# Programmer_HCS.net
KiCad netlist of a schematic drawn in EAGLE
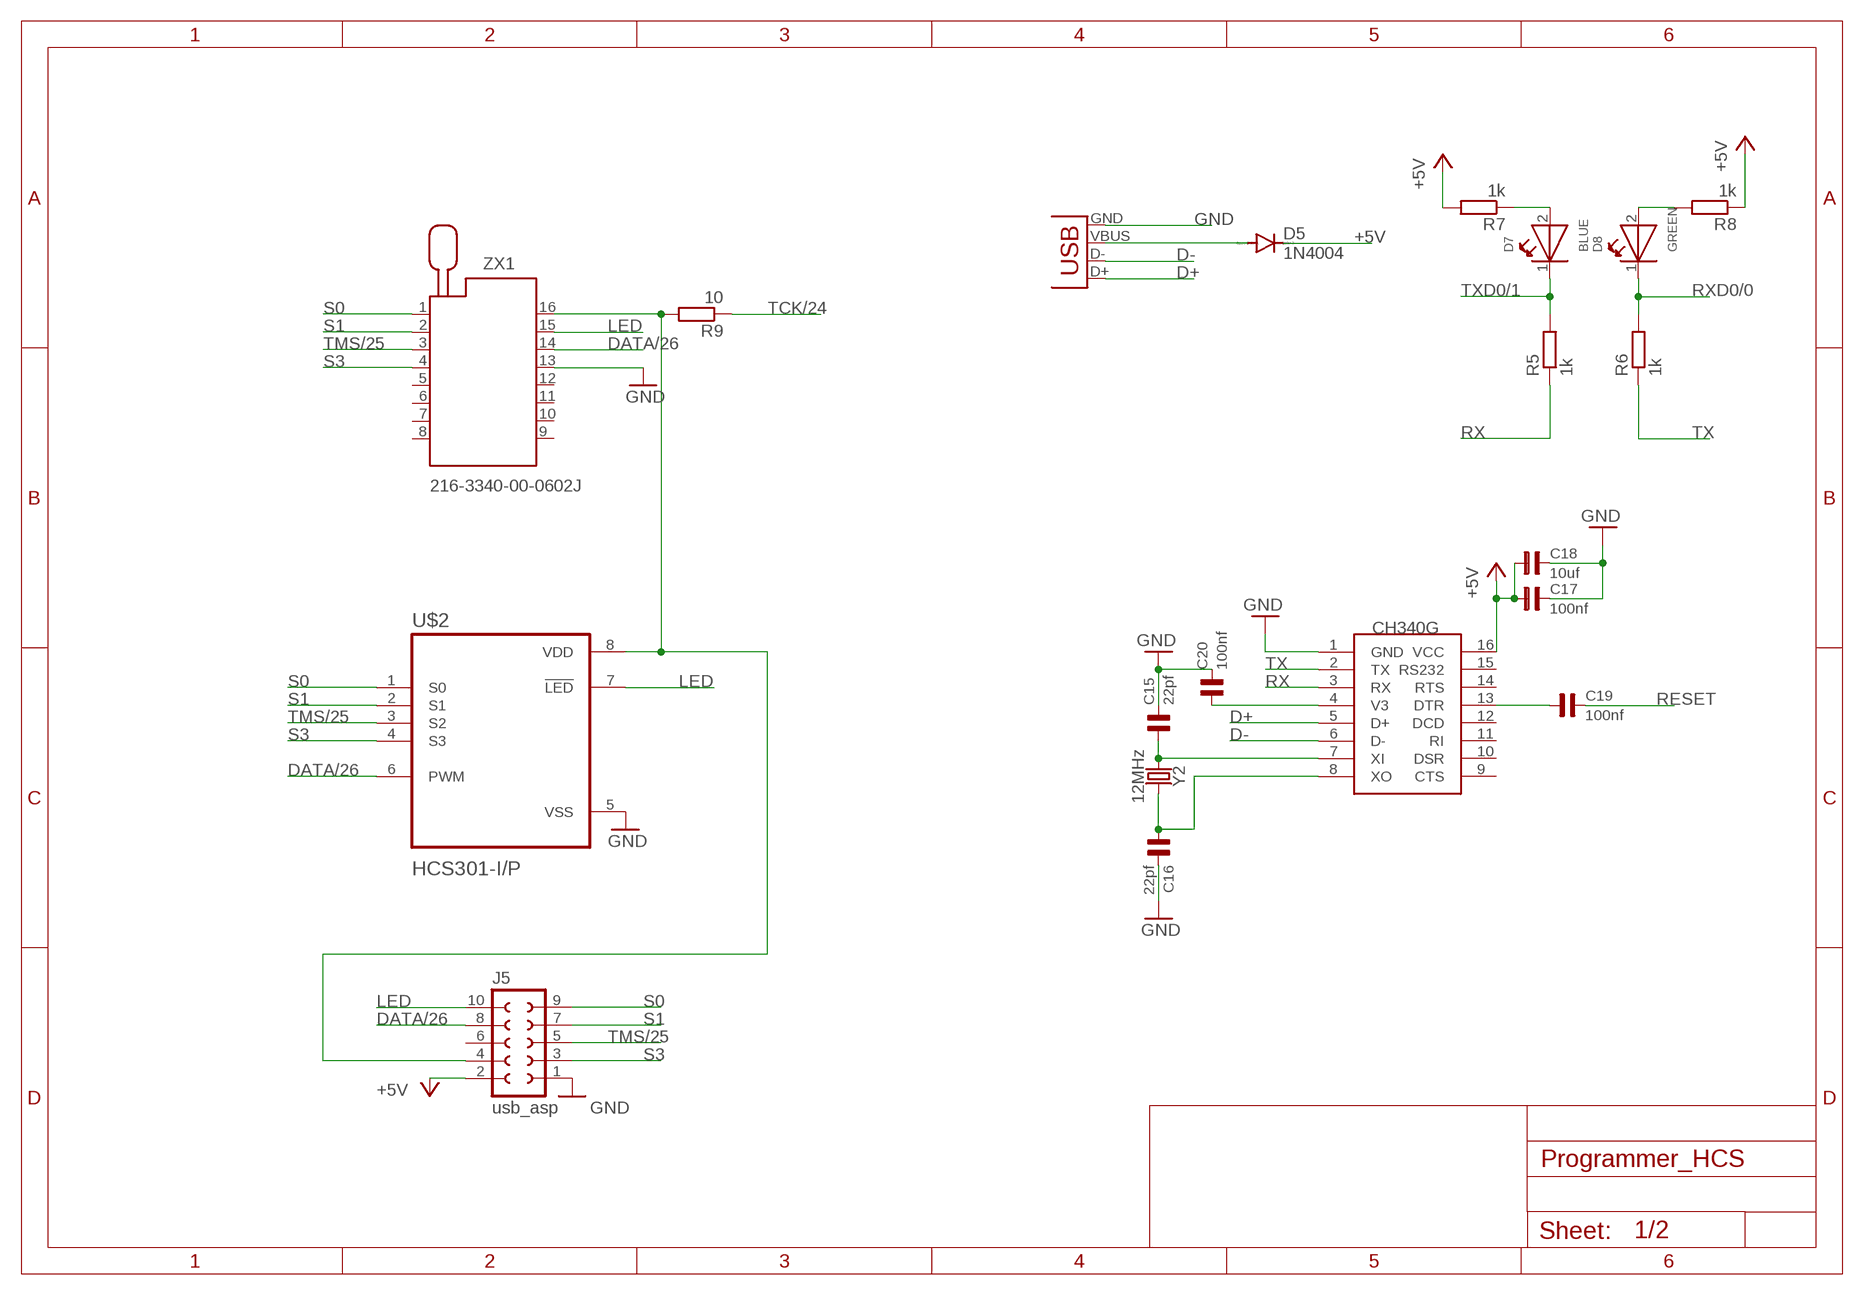
[diagram p0: schematic, sheet 1]
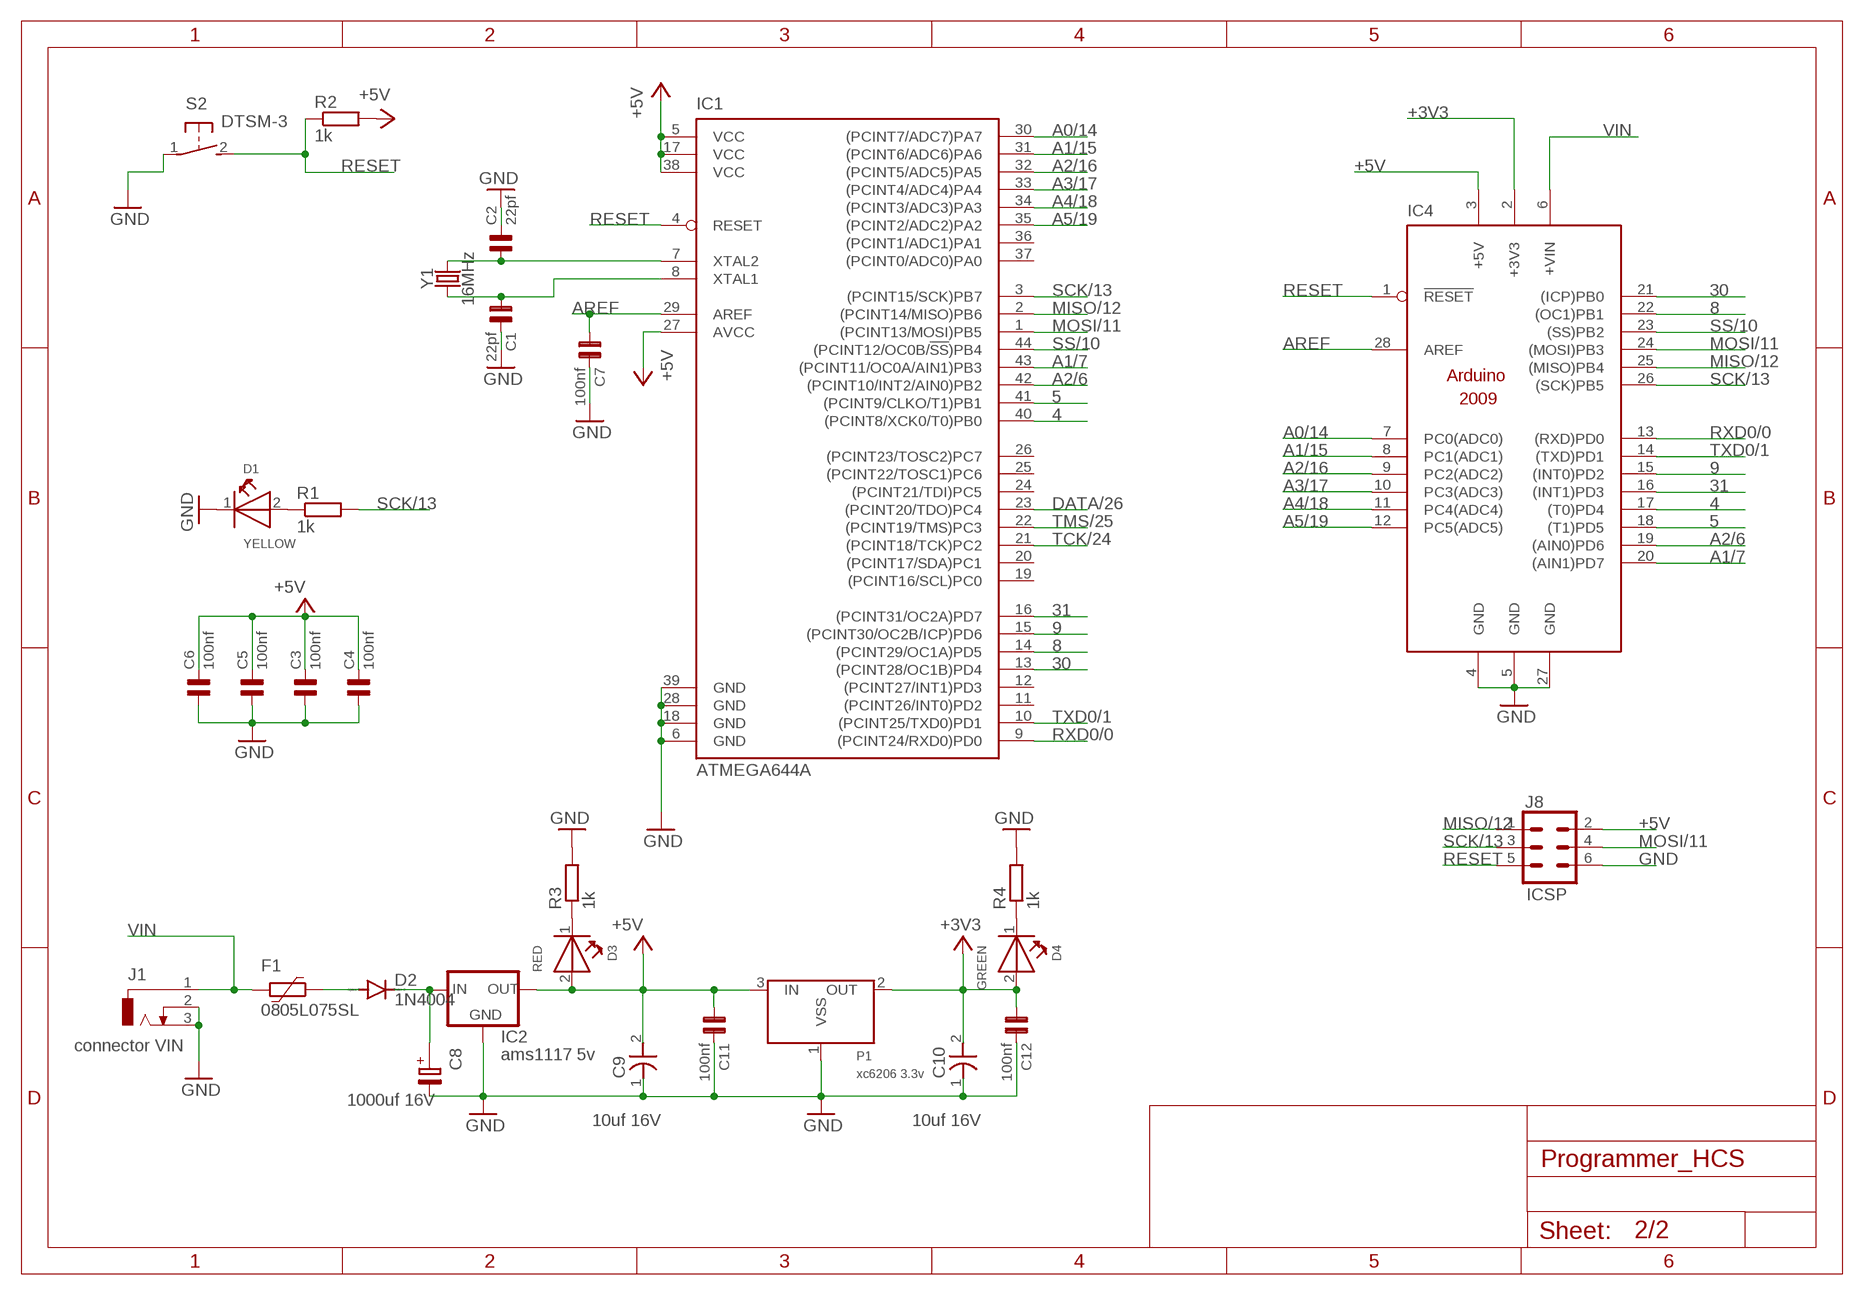
[diagram p1: schematic, sheet 2]

(export (version "E")
  (design (tool "Eeschema 10.0.6"))
  (components
    (comp (ref "C15")
      (value "22pf")
      (footprint "eagle-import:0805")
      (libsource (lib "eagle-import") (part "C0805"))
    )
    (comp (ref "C16")
      (value "22pf")
      (footprint "eagle-import:0805")
      (libsource (lib "eagle-import") (part "C0805"))
    )
    (comp (ref "C17")
      (value "100nf")
      (footprint "eagle-import:0805")
      (libsource (lib "eagle-import") (part "C0805"))
    )
    (comp (ref "C18")
      (value "10uf")
      (footprint "eagle-import:0805")
      (libsource (lib "eagle-import") (part "C0805"))
    )
    (comp (ref "C19")
      (value "100nf")
      (footprint "eagle-import:0805")
      (libsource (lib "eagle-import") (part "C0805"))
    )
    (comp (ref "C20")
      (value "100nf")
      (footprint "eagle-import:0805")
      (libsource (lib "eagle-import") (part "C0805"))
    )
    (comp (ref "D5")
      (value "1N4004")
      (footprint "eagle-import:DO214AA")
      (libsource (lib "eagle-import") (part "DIODE-DO214AA"))
    )
    (comp (ref "D7")
      (value "BLUE")
      (footprint "eagle-import:0805")
      (fields
        (field (name "MANUFACTURER") "Würth Elektronik eiSos GmbH")
        (field (name "CREATED-BY") "Christin Otto")
      )
      (libsource (lib "eagle-import") (part "WL-SMCW-150080RS75000-R"))
    )
    (comp (ref "D8")
      (value "GREEN")
      (footprint "eagle-import:0805")
      (fields
        (field (name "MANUFACTURER") "Würth Elektronik eiSos GmbH")
        (field (name "CREATED-BY") "Christin Otto")
      )
      (libsource (lib "eagle-import") (part "WL-SMCW-150080RS75000-R"))
    )
    (comp (ref "J5")
      (value "usb_asp")
      (footprint "eagle-import:S10V")
      (libsource (lib "eagle-import") (part "SOCKET-10V"))
    )
    (comp (ref "R5")
      (value "1k")
      (footprint "eagle-import:R0805")
      (libsource (lib "eagle-import") (part "R-EU_R0805"))
    )
    (comp (ref "R6")
      (value "1k")
      (footprint "eagle-import:R0805")
      (libsource (lib "eagle-import") (part "R-EU_R0805"))
    )
    (comp (ref "R7")
      (value "1k")
      (footprint "eagle-import:R0805")
      (libsource (lib "eagle-import") (part "R-EU_R0805"))
    )
    (comp (ref "R8")
      (value "1k")
      (footprint "eagle-import:R0805")
      (libsource (lib "eagle-import") (part "R-EU_R0805"))
    )
    (comp (ref "R9")
      (value "10")
      (footprint "eagle-import:R0805")
      (libsource (lib "eagle-import") (part "R-EU_R0805"))
    )
    (comp (ref "U$1")
      (value "CH340G")
      (footprint "eagle-import:SOIC16")
      (libsource (lib "eagle-import") (part "CH340G"))
    )
    (comp (ref "U$2")
      (value "HCS301-I/P")
      (footprint "eagle-import:DIP787W46P254L927H533Q8")
      (fields (field (name "MF") "Microchip"))
      (libsource (lib "eagle-import") (part "HCS301-I/P"))
    )
    (comp (ref "X1")
      (value "USB-B-H")
      (footprint "eagle-import:USB-B-H")
      (libsource (lib "eagle-import") (part "USB-B-H"))
    )
    (comp (ref "Y2")
      (value "12MHz")
      (footprint "eagle-import:HC49US")
      (libsource (lib "eagle-import") (part "CRYSTAL-16MHZPTH-HC49US"))
    )
    (comp (ref "ZX1")
      (value "216-3340-00-0602J")
      (footprint "eagle-import:216-3340-00-0602J")
      (fields (field (name "MF") "3M"))
      (libsource (lib "eagle-import") (part "216-3340-00-0602J"))
    )
    (comp (ref "C1")
      (value "22pf")
      (footprint "eagle-import:0805")
      (libsource (lib "eagle-import") (part "C0805"))
    )
    (comp (ref "C2")
      (value "22pf")
      (footprint "eagle-import:0805")
      (libsource (lib "eagle-import") (part "C0805"))
    )
    (comp (ref "C3")
      (value "100nf")
      (footprint "eagle-import:0805")
      (libsource (lib "eagle-import") (part "C0805"))
    )
    (comp (ref "C4")
      (value "100nf")
      (footprint "eagle-import:0805")
      (libsource (lib "eagle-import") (part "C0805"))
    )
    (comp (ref "C5")
      (value "100nf")
      (footprint "eagle-import:0805")
      (libsource (lib "eagle-import") (part "C0805"))
    )
    (comp (ref "C6")
      (value "100nf")
      (footprint "eagle-import:0805")
      (libsource (lib "eagle-import") (part "C0805"))
    )
    (comp (ref "C7")
      (value "100nf")
      (footprint "eagle-import:0805")
      (libsource (lib "eagle-import") (part "C0805"))
    )
    (comp (ref "C8")
      (value "1000uf 16V")
      (footprint "eagle-import:SV-G")
      (libsource (lib "eagle-import") (part "C-PR-SMD-SV-G"))
    )
    (comp (ref "C9")
      (value "10uf 16V")
      (footprint "eagle-import:6032")
      (libsource (lib "eagle-import") (part "CP6032"))
    )
    (comp (ref "C10")
      (value "10uf 16V")
      (footprint "eagle-import:6032")
      (libsource (lib "eagle-import") (part "CP6032"))
    )
    (comp (ref "C11")
      (value "100nf")
      (footprint "eagle-import:0805")
      (libsource (lib "eagle-import") (part "C0805"))
    )
    (comp (ref "C12")
      (value "100nf")
      (footprint "eagle-import:0805")
      (libsource (lib "eagle-import") (part "C0805"))
    )
    (comp (ref "D1")
      (value "YELLOW")
      (footprint "eagle-import:3528-2PIN")
      (fields
        (field (name "MANUFACTURER") "Würth Elektronik eiSos GmbH")
        (field (name "CREATED-BY") "Christin Otto")
      )
      (libsource (lib "eagle-import") (part "WL-SMTW-150141AS73100-A"))
    )
    (comp (ref "D2")
      (value "1N4004")
      (footprint "eagle-import:DO-214AC")
      (libsource (lib "eagle-import") (part "DIODE-DO-214AC"))
    )
    (comp (ref "D3")
      (value "RED")
      (footprint "eagle-import:3528-2PIN")
      (fields
        (field (name "MANUFACTURER") "Würth Elektronik eiSos GmbH")
        (field (name "CREATED-BY") "Christin Otto")
      )
      (libsource (lib "eagle-import") (part "WL-SMTW-150141AS73100-A"))
    )
    (comp (ref "D4")
      (value "GREEN")
      (footprint "eagle-import:3528-2PIN")
      (fields
        (field (name "MANUFACTURER") "Würth Elektronik eiSos GmbH")
        (field (name "CREATED-BY") "Christin Otto")
      )
      (libsource (lib "eagle-import") (part "WL-SMTW-150141AS73100-A"))
    )
    (comp (ref "F1")
      (value "0805L075SL")
      (footprint "eagle-import:0805L")
      (fields (field (name "MF") "Littelfuse"))
      (libsource (lib "eagle-import") (part "?0805L075SL"))
    )
    (comp (ref "IC1")
      (value "ATMEGA644A")
      (footprint "eagle-import:TQFP44")
      (fields (field (name "MPN") "ATMEGA644PV-10AU"))
      (libsource (lib "eagle-import") (part "ATMEGA644A"))
    )
    (comp (ref "IC2")
      (value "ams1117 5v")
      (footprint "eagle-import:SOT223")
      (libsource (lib "eagle-import") (part "LM1117"))
    )
    (comp (ref "IC4")
      (value "UNO")
      (footprint "eagle-import:ARDUINO2009")
      (libsource (lib "eagle-import") (part "ARDUINO2009_PIN_10"))
    )
    (comp (ref "J1")
      (value "connector VIN")
      (footprint "eagle-import:DCJ0303")
      (libsource (lib "eagle-import") (part "DCJ0303"))
    )
    (comp (ref "J8")
      (value "ICSP")
      (footprint "eagle-import:2X3")
      (libsource (lib "eagle-import") (part "CONN_03X2FEMALE"))
    )
    (comp (ref "P1")
      (value "xc6206 3.3v")
      (footprint "eagle-import:XC6206_SOT-23")
      (libsource (lib "eagle-import") (part "XC6206SOT-23"))
    )
    (comp (ref "R1")
      (value "1k")
      (footprint "eagle-import:R0805")
      (libsource (lib "eagle-import") (part "R-EU_R0805"))
    )
    (comp (ref "R2")
      (value "1k")
      (footprint "eagle-import:R0805")
      (libsource (lib "eagle-import") (part "R-EU_R0805"))
    )
    (comp (ref "R3")
      (value "1k")
      (footprint "eagle-import:R0805")
      (libsource (lib "eagle-import") (part "R-EU_R0805"))
    )
    (comp (ref "R4")
      (value "1k")
      (footprint "eagle-import:R0805")
      (libsource (lib "eagle-import") (part "R-EU_R0805"))
    )
    (comp (ref "S2")
      (value "DTSM-3")
      (footprint "eagle-import:DTSM-3")
      (libsource (lib "eagle-import") (part "DTSM-3"))
    )
    (comp (ref "Y1")
      (value "16MHz")
      (footprint "eagle-import:HC49US")
      (libsource (lib "eagle-import") (part "CRYSTAL-16MHZPTH-HC49US"))
    )
  )
  (nets
    (net (code "1") (name "+3V3") (class "Default")
      (node (ref "C10") (pin "2") (pinfunction "+_2") (pintype "passive"))
      (node (ref "C12") (pin "1") (pinfunction "1_1") (pintype "passive"))
      (node (ref "D4") (pin "2") (pinfunction "A_2") (pintype "bidirectional"))
      (node (ref "IC4") (pin "2") (pinfunction "+3V3_2") (pintype "power_in"))
      (node (ref "P1") (pin "2") (pinfunction "OUT_2") (pintype "bidirectional"))
    )
    (net (code "2") (name "+5V") (class "Default")
      (node (ref "C11") (pin "1") (pinfunction "1_1") (pintype "passive"))
      (node (ref "C17") (pin "1") (pinfunction "1_1") (pintype "passive"))
      (node (ref "C18") (pin "1") (pinfunction "1_1") (pintype "passive"))
      (node (ref "C3") (pin "2") (pinfunction "2_2") (pintype "passive"))
      (node (ref "C4") (pin "2") (pinfunction "2_2") (pintype "passive"))
      (node (ref "C5") (pin "2") (pinfunction "2_2") (pintype "passive"))
      (node (ref "C6") (pin "2") (pinfunction "2_2") (pintype "passive"))
      (node (ref "C9") (pin "2") (pinfunction "+_2") (pintype "passive"))
      (node (ref "D3") (pin "2") (pinfunction "A_2") (pintype "bidirectional"))
      (node (ref "D5") (pin "C") (pinfunction "C_C") (pintype "passive"))
      (node (ref "IC1") (pin "17") (pinfunction "VCC_17") (pintype "power_in"))
      (node (ref "IC1") (pin "27") (pinfunction "AVCC_27") (pintype "power_in"))
      (node (ref "IC1") (pin "38") (pinfunction "VCC_38") (pintype "power_in"))
      (node (ref "IC1") (pin "5") (pinfunction "VCC_5") (pintype "power_in"))
      (node (ref "IC2") (pin "2") (pinfunction "OUT_2") (pintype "passive"))
      (node (ref "IC4") (pin "3") (pinfunction "+5V_3") (pintype "power_in"))
      (node (ref "J5") (pin "2") (pinfunction "2_2") (pintype "passive"))
      (node (ref "J8") (pin "2") (pinfunction "2_2") (pintype "bidirectional"))
      (node (ref "P1") (pin "3") (pinfunction "IN_3") (pintype "bidirectional"))
      (node (ref "R2") (pin "2") (pinfunction "2_2") (pintype "passive"))
      (node (ref "R7") (pin "2") (pinfunction "2_2") (pintype "passive"))
      (node (ref "R8") (pin "1") (pinfunction "1_1") (pintype "passive"))
      (node (ref "U$1") (pin "16") (pinfunction "VCC_16") (pintype "bidirectional"))
    )
    (net (code "3") (name "4") (class "Default")
      (node (ref "IC1") (pin "40") (pinfunction "(PCINT8/XCK0/T0)PB0_40") (pintype "bidirectional"))
      (node (ref "IC4") (pin "17") (pinfunction "(T0)PD4_17") (pintype "bidirectional"))
    )
    (net (code "4") (name "5") (class "Default")
      (node (ref "IC1") (pin "41") (pinfunction "(PCINT9/CLKO/T1)PB1_41") (pintype "bidirectional"))
      (node (ref "IC4") (pin "18") (pinfunction "(T1)PD5_18") (pintype "bidirectional"))
    )
    (net (code "5") (name "8") (class "Default")
      (node (ref "IC1") (pin "14") (pinfunction "(PCINT29/OC1A)PD5_14") (pintype "bidirectional"))
      (node (ref "IC4") (pin "22") (pinfunction "(OC1)PB1_22") (pintype "bidirectional"))
    )
    (net (code "6") (name "9") (class "Default")
      (node (ref "IC1") (pin "15") (pinfunction "(PCINT30/OC2B/ICP)PD6_15") (pintype "bidirectional"))
      (node (ref "IC4") (pin "15") (pinfunction "(INT0)PD2_15") (pintype "bidirectional"))
    )
    (net (code "7") (name "30") (class "Default")
      (node (ref "IC1") (pin "13") (pinfunction "(PCINT28/OC1B)PD4_13") (pintype "bidirectional"))
      (node (ref "IC4") (pin "21") (pinfunction "(ICP)PB0_21") (pintype "bidirectional"))
    )
    (net (code "8") (name "31") (class "Default")
      (node (ref "IC1") (pin "16") (pinfunction "(PCINT31/OC2A)PD7_16") (pintype "bidirectional"))
      (node (ref "IC4") (pin "16") (pinfunction "(INT1)PD3_16") (pintype "bidirectional"))
    )
    (net (code "9") (name "A0{slash}14") (class "Default")
      (node (ref "IC1") (pin "30") (pinfunction "(PCINT7/ADC7)PA7_30") (pintype "bidirectional"))
      (node (ref "IC4") (pin "7") (pinfunction "PC0(ADC0)_7") (pintype "bidirectional"))
    )
    (net (code "10") (name "A1{slash}7") (class "Default")
      (node (ref "IC1") (pin "43") (pinfunction "(PCINT11/OC0A/AIN1)PB3_43") (pintype "bidirectional"))
      (node (ref "IC4") (pin "20") (pinfunction "(AIN1)PD7_20") (pintype "bidirectional"))
    )
    (net (code "11") (name "A1{slash}15") (class "Default")
      (node (ref "IC1") (pin "31") (pinfunction "(PCINT6/ADC6)PA6_31") (pintype "bidirectional"))
      (node (ref "IC4") (pin "8") (pinfunction "PC1(ADC1)_8") (pintype "bidirectional"))
    )
    (net (code "12") (name "A2{slash}6") (class "Default")
      (node (ref "IC1") (pin "42") (pinfunction "(PCINT10/INT2/AIN0)PB2_42") (pintype "bidirectional"))
      (node (ref "IC4") (pin "19") (pinfunction "(AIN0)PD6_19") (pintype "bidirectional"))
    )
    (net (code "13") (name "A2{slash}16") (class "Default")
      (node (ref "IC1") (pin "32") (pinfunction "(PCINT5/ADC5)PA5_32") (pintype "bidirectional"))
      (node (ref "IC4") (pin "9") (pinfunction "PC2(ADC2)_9") (pintype "bidirectional"))
    )
    (net (code "14") (name "A3{slash}17") (class "Default")
      (node (ref "IC1") (pin "33") (pinfunction "(PCINT4/ADC4)PA4_33") (pintype "bidirectional"))
      (node (ref "IC4") (pin "10") (pinfunction "PC3(ADC3)_10") (pintype "bidirectional"))
    )
    (net (code "15") (name "A4{slash}18") (class "Default")
      (node (ref "IC1") (pin "34") (pinfunction "(PCINT3/ADC3)PA3_34") (pintype "bidirectional"))
      (node (ref "IC4") (pin "11") (pinfunction "PC4(ADC4)_11") (pintype "bidirectional"))
    )
    (net (code "16") (name "A5{slash}19") (class "Default")
      (node (ref "IC1") (pin "35") (pinfunction "(PCINT2/ADC2)PA2_35") (pintype "bidirectional"))
      (node (ref "IC4") (pin "12") (pinfunction "PC5(ADC5)_12") (pintype "bidirectional"))
    )
    (net (code "17") (name "AREF") (class "Default")
      (node (ref "C7") (pin "1") (pinfunction "1_1") (pintype "passive"))
      (node (ref "IC1") (pin "29") (pinfunction "AREF_29") (pintype "passive"))
      (node (ref "IC4") (pin "28") (pinfunction "AREF_28") (pintype "bidirectional"))
    )
    (net (code "18") (name "D+") (class "Default")
      (node (ref "U$1") (pin "5") (pinfunction "D+_5") (pintype "bidirectional"))
      (node (ref "X1") (pin "D+") (pinfunction "D+_D+") (pintype "bidirectional"))
    )
    (net (code "19") (name "D-") (class "Default")
      (node (ref "U$1") (pin "6") (pinfunction "D-_6") (pintype "bidirectional"))
      (node (ref "X1") (pin "D-") (pinfunction "D-_D-") (pintype "bidirectional"))
    )
    (net (code "20") (name "DATA{slash}26") (class "Default")
      (node (ref "IC1") (pin "23") (pinfunction "(PCINT20/TDO)PC4_23") (pintype "output"))
      (node (ref "J5") (pin "8") (pinfunction "8_8") (pintype "passive"))
      (node (ref "U$2") (pin "6") (pinfunction "PWM_6") (pintype "bidirectional"))
      (node (ref "ZX1") (pin "14") (pinfunction "14_14") (pintype "passive"))
    )
    (net (code "21") (name "GND") (class "Default")
      (node (ref "C1") (pin "2") (pinfunction "2_2") (pintype "passive"))
      (node (ref "C10") (pin "1") (pinfunction "-_1") (pintype "passive"))
      (node (ref "C11") (pin "2") (pinfunction "2_2") (pintype "passive"))
      (node (ref "C12") (pin "2") (pinfunction "2_2") (pintype "passive"))
      (node (ref "C15") (pin "2") (pinfunction "2_2") (pintype "passive"))
      (node (ref "C16") (pin "2") (pinfunction "2_2") (pintype "passive"))
      (node (ref "C17") (pin "2") (pinfunction "2_2") (pintype "passive"))
      (node (ref "C18") (pin "2") (pinfunction "2_2") (pintype "passive"))
      (node (ref "C2") (pin "2") (pinfunction "2_2") (pintype "passive"))
      (node (ref "C20") (pin "2") (pinfunction "2_2") (pintype "passive"))
      (node (ref "C3") (pin "1") (pinfunction "1_1") (pintype "passive"))
      (node (ref "C4") (pin "1") (pinfunction "1_1") (pintype "passive"))
      (node (ref "C5") (pin "1") (pinfunction "1_1") (pintype "passive"))
      (node (ref "C6") (pin "1") (pinfunction "1_1") (pintype "passive"))
      (node (ref "C7") (pin "2") (pinfunction "2_2") (pintype "passive"))
      (node (ref "C8") (pin "-") (pinfunction "-_-") (pintype "passive"))
      (node (ref "C9") (pin "1") (pinfunction "-_1") (pintype "passive"))
      (node (ref "D1") (pin "1") (pinfunction "K_1") (pintype "bidirectional"))
      (node (ref "IC1") (pin "18") (pinfunction "GND_18") (pintype "power_in"))
      (node (ref "IC1") (pin "28") (pinfunction "GND_28") (pintype "power_in"))
      (node (ref "IC1") (pin "39") (pinfunction "GND_39") (pintype "power_in"))
      (node (ref "IC1") (pin "6") (pinfunction "GND_6") (pintype "power_in"))
      (node (ref "IC2") (pin "1") (pinfunction "GND_1") (pintype "input"))
      (node (ref "IC4") (pin "27") (pinfunction "GND_27") (pintype "power_in"))
      (node (ref "IC4") (pin "4") (pinfunction "GND_4") (pintype "power_in"))
      (node (ref "IC4") (pin "5") (pinfunction "GND_5") (pintype "power_in"))
      (node (ref "J1") (pin "2") (pinfunction "2_2") (pintype "passive"))
      (node (ref "J1") (pin "3") (pinfunction "3_3") (pintype "passive"))
      (node (ref "J5") (pin "1") (pinfunction "1_1") (pintype "passive"))
      (node (ref "J8") (pin "6") (pinfunction "6_6") (pintype "bidirectional"))
      (node (ref "P1") (pin "1") (pinfunction "VSS_1") (pintype "bidirectional"))
      (node (ref "R3") (pin "2") (pinfunction "2_2") (pintype "passive"))
      (node (ref "R4") (pin "2") (pinfunction "2_2") (pintype "passive"))
      (node (ref "S2") (pin "1") (pinfunction "1_1") (pintype "passive"))
      (node (ref "U$1") (pin "1") (pinfunction "GND_1") (pintype "bidirectional"))
      (node (ref "U$2") (pin "5") (pinfunction "VSS_5") (pintype "power_in"))
      (node (ref "X1") (pin "GND") (pinfunction "GND_GND") (pintype "bidirectional"))
      (node (ref "ZX1") (pin "13") (pinfunction "13_13") (pintype "passive"))
    )
    (net (code "22") (name "LED") (class "Default")
      (node (ref "J5") (pin "10") (pinfunction "10_10") (pintype "passive"))
      (node (ref "U$2") (pin "7") (pinfunction "~{LED}_7") (pintype "output"))
      (node (ref "ZX1") (pin "15") (pinfunction "15_15") (pintype "passive"))
    )
    (net (code "23") (name "MISO{slash}12") (class "Default")
      (node (ref "IC1") (pin "2") (pinfunction "(PCINT14/MISO)PB6_2") (pintype "bidirectional"))
      (node (ref "IC4") (pin "25") (pinfunction "(MISO)PB4_25") (pintype "bidirectional"))
      (node (ref "J8") (pin "1") (pinfunction "1_1") (pintype "bidirectional"))
    )
    (net (code "24") (name "MOSI{slash}11") (class "Default")
      (node (ref "IC1") (pin "1") (pinfunction "(PCINT13/MOSI)PB5_1") (pintype "bidirectional"))
      (node (ref "IC4") (pin "24") (pinfunction "(MOSI)PB3_24") (pintype "bidirectional"))
      (node (ref "J8") (pin "4") (pinfunction "4_4") (pintype "bidirectional"))
    )
    (net (code "25") (name "Net-(D1-A)") (class "Default")
      (node (ref "D1") (pin "2") (pinfunction "A_2") (pintype "bidirectional"))
      (node (ref "R1") (pin "1") (pinfunction "1_1") (pintype "passive"))
    )
    (net (code "26") (name "Net-(D2-PadA)") (class "Default")
      (node (ref "D2") (pin "A") (pinfunction "A_A") (pintype "passive"))
      (node (ref "F1") (pin "1") (pinfunction "1_1") (pintype "passive"))
    )
    (net (code "27") (name "Net-(D3-K)") (class "Default")
      (node (ref "D3") (pin "1") (pinfunction "K_1") (pintype "bidirectional"))
      (node (ref "R3") (pin "1") (pinfunction "1_1") (pintype "passive"))
    )
    (net (code "28") (name "Net-(D4-K)") (class "Default")
      (node (ref "D4") (pin "1") (pinfunction "K_1") (pintype "bidirectional"))
      (node (ref "R4") (pin "1") (pinfunction "1_1") (pintype "passive"))
    )
    (net (code "29") (name "Net-(D5-PadA)") (class "Default")
      (node (ref "D5") (pin "A") (pinfunction "A_A") (pintype "passive"))
      (node (ref "X1") (pin "VBUS") (pinfunction "VBUS_VBUS") (pintype "bidirectional"))
    )
    (net (code "30") (name "Net-(D7-A)") (class "Default")
      (node (ref "D7") (pin "2") (pinfunction "A_2") (pintype "bidirectional"))
      (node (ref "R7") (pin "1") (pinfunction "1_1") (pintype "passive"))
    )
    (net (code "31") (name "Net-(D8-A)") (class "Default")
      (node (ref "D8") (pin "2") (pinfunction "A_2") (pintype "bidirectional"))
      (node (ref "R8") (pin "2") (pinfunction "2_2") (pintype "passive"))
    )
    (net (code "32") (name "Net-(IC1-XTAL1)") (class "Default")
      (node (ref "C1") (pin "1") (pinfunction "1_1") (pintype "passive"))
      (node (ref "IC1") (pin "8") (pinfunction "XTAL1_8") (pintype "bidirectional"))
      (node (ref "Y1") (pin "1") (pinfunction "1_1") (pintype "passive"))
    )
    (net (code "33") (name "Net-(IC1-XTAL2)") (class "Default")
      (node (ref "C2") (pin "1") (pinfunction "1_1") (pintype "passive"))
      (node (ref "IC1") (pin "7") (pinfunction "XTAL2_7") (pintype "bidirectional"))
      (node (ref "Y1") (pin "2") (pinfunction "2_2") (pintype "passive"))
    )
    (net (code "34") (name "Net-(IC2-IN)") (class "Default")
      (node (ref "C8") (pin "+") (pinfunction "+_+") (pintype "passive"))
      (node (ref "D2") (pin "C") (pinfunction "C_C") (pintype "passive"))
      (node (ref "IC2") (pin "3") (pinfunction "IN_3") (pintype "input"))
    )
    (net (code "35") (name "Net-(U$1-DTR)") (class "Default")
      (node (ref "C19") (pin "1") (pinfunction "1_1") (pintype "passive"))
      (node (ref "U$1") (pin "13") (pinfunction "DTR_13") (pintype "bidirectional"))
    )
    (net (code "36") (name "Net-(U$1-V3)") (class "Default")
      (node (ref "C20") (pin "1") (pinfunction "1_1") (pintype "passive"))
      (node (ref "U$1") (pin "4") (pinfunction "V3_4") (pintype "bidirectional"))
    )
    (net (code "37") (name "Net-(U$1-XI)") (class "Default")
      (node (ref "C15") (pin "1") (pinfunction "1_1") (pintype "passive"))
      (node (ref "U$1") (pin "7") (pinfunction "XI_7") (pintype "bidirectional"))
      (node (ref "Y2") (pin "1") (pinfunction "1_1") (pintype "passive"))
    )
    (net (code "38") (name "Net-(U$1-XO)") (class "Default")
      (node (ref "C16") (pin "1") (pinfunction "1_1") (pintype "passive"))
      (node (ref "U$1") (pin "8") (pinfunction "XO_8") (pintype "bidirectional"))
      (node (ref "Y2") (pin "2") (pinfunction "2_2") (pintype "passive"))
    )
    (net (code "39") (name "Net-(U$2-VDD)") (class "Default")
      (node (ref "J5") (pin "4") (pinfunction "4_4") (pintype "passive"))
      (node (ref "R9") (pin "2") (pinfunction "2_2") (pintype "passive"))
      (node (ref "U$2") (pin "8") (pinfunction "VDD_8") (pintype "power_in"))
      (node (ref "ZX1") (pin "16") (pinfunction "16_16") (pintype "passive"))
    )
    (net (code "40") (name "RESET") (class "Default")
      (node (ref "C19") (pin "2") (pinfunction "2_2") (pintype "passive"))
      (node (ref "IC1") (pin "4") (pinfunction "RESET_4") (pintype "input"))
      (node (ref "IC4") (pin "1") (pinfunction "~{RESET}_1") (pintype "bidirectional"))
      (node (ref "J8") (pin "5") (pinfunction "5_5") (pintype "bidirectional"))
      (node (ref "R2") (pin "1") (pinfunction "1_1") (pintype "passive"))
      (node (ref "S2") (pin "2") (pinfunction "2_2") (pintype "passive"))
    )
    (net (code "41") (name "RX") (class "Default")
      (node (ref "R5") (pin "1") (pinfunction "1_1") (pintype "passive"))
      (node (ref "U$1") (pin "3") (pinfunction "RX_3") (pintype "bidirectional"))
    )
    (net (code "42") (name "RXD0{slash}0") (class "Default")
      (node (ref "D8") (pin "1") (pinfunction "K_1") (pintype "bidirectional"))
      (node (ref "IC1") (pin "9") (pinfunction "(PCINT24/RXD0)PD0_9") (pintype "bidirectional"))
      (node (ref "IC4") (pin "13") (pinfunction "(RXD)PD0_13") (pintype "bidirectional"))
      (node (ref "R6") (pin "2") (pinfunction "2_2") (pintype "passive"))
    )
    (net (code "43") (name "S0") (class "Default")
      (node (ref "J5") (pin "9") (pinfunction "9_9") (pintype "passive"))
      (node (ref "U$2") (pin "1") (pinfunction "S0_1") (pintype "input"))
      (node (ref "ZX1") (pin "1") (pinfunction "1_1") (pintype "passive"))
    )
    (net (code "44") (name "S1") (class "Default")
      (node (ref "J5") (pin "7") (pinfunction "7_7") (pintype "passive"))
      (node (ref "U$2") (pin "2") (pinfunction "S1_2") (pintype "input"))
      (node (ref "ZX1") (pin "2") (pinfunction "2_2") (pintype "passive"))
    )
    (net (code "45") (name "S3") (class "Default")
      (node (ref "J5") (pin "3") (pinfunction "3_3") (pintype "passive"))
      (node (ref "U$2") (pin "4") (pinfunction "S3_4") (pintype "input"))
      (node (ref "ZX1") (pin "4") (pinfunction "4_4") (pintype "passive"))
    )
    (net (code "46") (name "SCK{slash}13") (class "Default")
      (node (ref "IC1") (pin "3") (pinfunction "(PCINT15/SCK)PB7_3") (pintype "bidirectional"))
      (node (ref "IC4") (pin "26") (pinfunction "(SCK)PB5_26") (pintype "bidirectional"))
      (node (ref "J8") (pin "3") (pinfunction "3_3") (pintype "bidirectional"))
      (node (ref "R1") (pin "2") (pinfunction "2_2") (pintype "passive"))
    )
    (net (code "47") (name "SS{slash}10") (class "Default")
      (node (ref "IC1") (pin "44") (pinfunction "(PCINT12/OC0B/~{SS})PB4_44") (pintype "bidirectional"))
      (node (ref "IC4") (pin "23") (pinfunction "(SS)PB2_23") (pintype "bidirectional"))
    )
    (net (code "48") (name "TCK{slash}24") (class "Default")
      (node (ref "IC1") (pin "21") (pinfunction "(PCINT18/TCK)PC2_21") (pintype "output"))
      (node (ref "R9") (pin "1") (pinfunction "1_1") (pintype "passive"))
    )
    (net (code "49") (name "TMS{slash}25") (class "Default")
      (node (ref "IC1") (pin "22") (pinfunction "(PCINT19/TMS)PC3_22") (pintype "output"))
      (node (ref "J5") (pin "5") (pinfunction "5_5") (pintype "passive"))
      (node (ref "U$2") (pin "3") (pinfunction "S2_3") (pintype "input"))
      (node (ref "ZX1") (pin "3") (pinfunction "3_3") (pintype "passive"))
    )
    (net (code "50") (name "TX") (class "Default")
      (node (ref "R6") (pin "1") (pinfunction "1_1") (pintype "passive"))
      (node (ref "U$1") (pin "2") (pinfunction "TX_2") (pintype "bidirectional"))
    )
    (net (code "51") (name "TXD0{slash}1") (class "Default")
      (node (ref "D7") (pin "1") (pinfunction "K_1") (pintype "bidirectional"))
      (node (ref "IC1") (pin "10") (pinfunction "(PCINT25/TXD0)PD1_10") (pintype "bidirectional"))
      (node (ref "IC4") (pin "14") (pinfunction "(TXD)PD1_14") (pintype "bidirectional"))
      (node (ref "R5") (pin "2") (pinfunction "2_2") (pintype "passive"))
    )
    (net (code "52") (name "VIN") (class "Default")
      (node (ref "F1") (pin "2") (pinfunction "2_2") (pintype "passive"))
      (node (ref "IC4") (pin "6") (pinfunction "+VIN_6") (pintype "bidirectional"))
      (node (ref "J1") (pin "1") (pinfunction "1_1") (pintype "passive"))
    )
    (net (code "53") (name "unconnected-(IC1-(PCINT0{slash}ADC0)PA0-Pad37)") (class "Default")
      (node (ref "IC1") (pin "37") (pinfunction "(PCINT0/ADC0)PA0_37") (pintype "bidirectional"))
    )
    (net (code "54") (name "unconnected-(IC1-(PCINT1{slash}ADC1)PA1-Pad36)") (class "Default")
      (node (ref "IC1") (pin "36") (pinfunction "(PCINT1/ADC1)PA1_36") (pintype "bidirectional"))
    )
    (net (code "55") (name "unconnected-(IC1-(PCINT16{slash}SCL)PC0-Pad19)") (class "Default")
      (node (ref "IC1") (pin "19") (pinfunction "(PCINT16/SCL)PC0_19") (pintype "output"))
    )
    (net (code "56") (name "unconnected-(IC1-(PCINT17{slash}SDA)PC1-Pad20)") (class "Default")
      (node (ref "IC1") (pin "20") (pinfunction "(PCINT17/SDA)PC1_20") (pintype "output"))
    )
    (net (code "57") (name "unconnected-(IC1-(PCINT21{slash}TDI)PC5-Pad24)") (class "Default")
      (node (ref "IC1") (pin "24") (pinfunction "(PCINT21/TDI)PC5_24") (pintype "output"))
    )
    (net (code "58") (name "unconnected-(IC1-(PCINT22{slash}TOSC1)PC6-Pad25)") (class "Default")
      (node (ref "IC1") (pin "25") (pinfunction "(PCINT22/TOSC1)PC6_25") (pintype "output"))
    )
    (net (code "59") (name "unconnected-(IC1-(PCINT23{slash}TOSC2)PC7-Pad26)") (class "Default")
      (node (ref "IC1") (pin "26") (pinfunction "(PCINT23/TOSC2)PC7_26") (pintype "output"))
    )
    (net (code "60") (name "unconnected-(IC1-(PCINT26{slash}INT0)PD2-Pad11)") (class "Default")
      (node (ref "IC1") (pin "11") (pinfunction "(PCINT26/INT0)PD2_11") (pintype "bidirectional"))
    )
    (net (code "61") (name "unconnected-(IC1-(PCINT27{slash}INT1)PD3-Pad12)") (class "Default")
      (node (ref "IC1") (pin "12") (pinfunction "(PCINT27/INT1)PD3_12") (pintype "bidirectional"))
    )
    (net (code "62") (name "unconnected-(J5-Pad6)") (class "Default")
      (node (ref "J5") (pin "6") (pinfunction "6_6") (pintype "passive"))
    )
    (net (code "63") (name "unconnected-(U$1-CTS-Pad9)") (class "Default")
      (node (ref "U$1") (pin "9") (pinfunction "CTS_9") (pintype "bidirectional"))
    )
    (net (code "64") (name "unconnected-(U$1-DCD-Pad12)") (class "Default")
      (node (ref "U$1") (pin "12") (pinfunction "DCD_12") (pintype "bidirectional"))
    )
    (net (code "65") (name "unconnected-(U$1-DSR-Pad10)") (class "Default")
      (node (ref "U$1") (pin "10") (pinfunction "DSR_10") (pintype "bidirectional"))
    )
    (net (code "66") (name "unconnected-(U$1-RI-Pad11)") (class "Default")
      (node (ref "U$1") (pin "11") (pinfunction "RI_11") (pintype "bidirectional"))
    )
    (net (code "67") (name "unconnected-(U$1-RS232-Pad15)") (class "Default")
      (node (ref "U$1") (pin "15") (pinfunction "RS232_15") (pintype "bidirectional"))
    )
    (net (code "68") (name "unconnected-(U$1-RTS-Pad14)") (class "Default")
      (node (ref "U$1") (pin "14") (pinfunction "RTS_14") (pintype "bidirectional"))
    )
    (net (code "69") (name "unconnected-(ZX1-Pad5)") (class "Default")
      (node (ref "ZX1") (pin "5") (pinfunction "5_5") (pintype "passive"))
    )
    (net (code "70") (name "unconnected-(ZX1-Pad6)") (class "Default")
      (node (ref "ZX1") (pin "6") (pinfunction "6_6") (pintype "passive"))
    )
    (net (code "71") (name "unconnected-(ZX1-Pad7)") (class "Default")
      (node (ref "ZX1") (pin "7") (pinfunction "7_7") (pintype "passive"))
    )
    (net (code "72") (name "unconnected-(ZX1-Pad8)") (class "Default")
      (node (ref "ZX1") (pin "8") (pinfunction "8_8") (pintype "passive"))
    )
    (net (code "73") (name "unconnected-(ZX1-Pad9)") (class "Default")
      (node (ref "ZX1") (pin "9") (pinfunction "9_9") (pintype "passive"))
    )
    (net (code "74") (name "unconnected-(ZX1-Pad10)") (class "Default")
      (node (ref "ZX1") (pin "10") (pinfunction "10_10") (pintype "passive"))
    )
    (net (code "75") (name "unconnected-(ZX1-Pad11)") (class "Default")
      (node (ref "ZX1") (pin "11") (pinfunction "11_11") (pintype "passive"))
    )
    (net (code "76") (name "unconnected-(ZX1-Pad12)") (class "Default")
      (node (ref "ZX1") (pin "12") (pinfunction "12_12") (pintype "passive"))
    )
  )
)
